# LED.net
KiCad netlist of a schematic drawn in Altium Designer
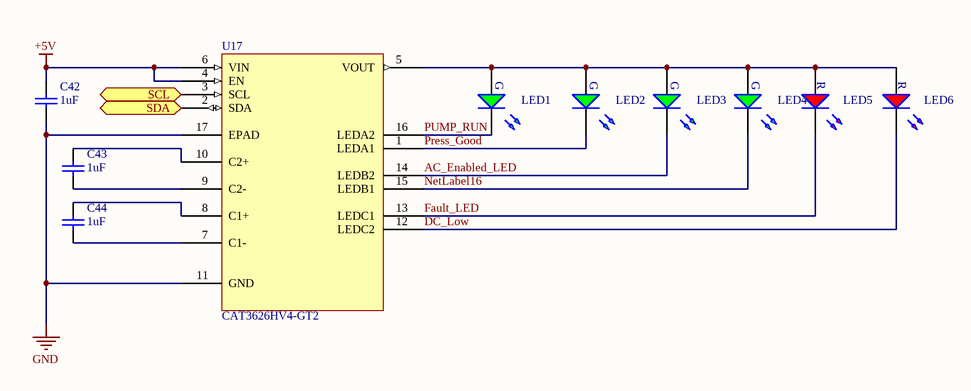
[diagram p0: LED.SchDoc]

(export (version "E")
  (design (tool "Eeschema 10.0.6"))
  (components
    (comp (ref "C42")
      (value "1uF")
      (footprint "0603C")
      (description "CAP CER 1UF 25V X5R 0603")
      (fields
        (field (name "MANUFACTURER") "Samsung Electro-Mechanics")
        (field (name "MANUFACTURER PART NUMBER") "CL10A105KA8NNNC")
      )
      (libsource (lib "RELECTRIFY-PARTSlib_A") (part "Capacitor"))
    )
    (comp (ref "C43")
      (value "1uF")
      (footprint "0603C")
      (description "CAP CER 1UF 25V X5R 0603")
      (fields
        (field (name "MANUFACTURER") "Samsung Electro-Mechanics")
        (field (name "MANUFACTURER PART NUMBER") "CL10A105KA8NNNC")
      )
      (libsource (lib "RELECTRIFY-PARTSlib_A") (part "Capacitor"))
    )
    (comp (ref "C44")
      (value "1uF")
      (footprint "0603C")
      (description "CAP CER 1UF 25V X5R 0603")
      (fields
        (field (name "MANUFACTURER") "Samsung Electro-Mechanics")
        (field (name "MANUFACTURER PART NUMBER") "CL10A105KA8NNNC")
      )
      (libsource (lib "RELECTRIFY-PARTSlib_A") (part "Capacitor"))
    )
    (comp (ref "LED1")
      (value "LED-G")
      (footprint "0805D")
      (description "LED GREEN CLEAR 0805 SMD")
      (fields
        (field (name "MANUFACTURER PART NUMBER") "150080GS75000")
        (field (name "MANUFACTURER") "Würth Elektronik")
      )
      (libsource (lib "RELECTRIFY-PARTSlib_A") (part "LED-G"))
    )
    (comp (ref "LED2")
      (value "LED-G")
      (footprint "0805D")
      (description "LED GREEN CLEAR 0805 SMD")
      (fields
        (field (name "MANUFACTURER PART NUMBER") "150080GS75000")
        (field (name "MANUFACTURER") "Würth Elektronik")
      )
      (libsource (lib "RELECTRIFY-PARTSlib_A") (part "LED-G"))
    )
    (comp (ref "LED3")
      (value "LED-G")
      (footprint "0805D")
      (description "LED GREEN CLEAR 0805 SMD")
      (fields
        (field (name "MANUFACTURER PART NUMBER") "150080GS75000")
        (field (name "MANUFACTURER") "Würth Elektronik")
      )
      (libsource (lib "RELECTRIFY-PARTSlib_A") (part "LED-G"))
    )
    (comp (ref "LED4")
      (value "LED-G")
      (footprint "0805D")
      (description "LED GREEN CLEAR 0805 SMD")
      (fields
        (field (name "MANUFACTURER PART NUMBER") "150080GS75000")
        (field (name "MANUFACTURER") "Würth Elektronik")
      )
      (libsource (lib "RELECTRIFY-PARTSlib_A") (part "LED-G"))
    )
    (comp (ref "LED5")
      (value "LED-R")
      (footprint "0805D")
      (description "LED RED CLEAR 0805 SMD")
      (fields
        (field (name "MANUFACTURER PART NUMBER") "150080RS75000")
        (field (name "MANUFACTURER") "Würth Elektronik")
      )
      (libsource (lib "RELECTRIFY-PARTSlib_A") (part "LED-R"))
    )
    (comp (ref "LED6")
      (value "LED-R")
      (footprint "0805D")
      (description "LED RED CLEAR 0805 SMD")
      (fields
        (field (name "MANUFACTURER PART NUMBER") "150080RS75000")
        (field (name "MANUFACTURER") "Würth Elektronik")
      )
      (libsource (lib "RELECTRIFY-PARTSlib_A") (part "LED-R"))
    )
    (comp (ref "U17")
      (value "CAT3626HV4-GT2")
      (footprint "CAT3626HV4-GT2")
      (fields
        (field (name "MANUFACTURER") "Onsemi")
        (field (name "COPYRIGHT") "Copyright (C) 2022 Ultra Librarian. All rights reserved.")
      )
      (libsource (lib "Database_library") (part "CAT3626HV4-GT2"))
    )
  )
  (nets
    (net (code "1") (name "+5V") (class "Default")
      (node (ref "C42") (pin "2") (pinfunction "2_2") (pintype "passive"))
      (node (ref "U17") (pin "4") (pinfunction "EN_4") (pintype "input"))
      (node (ref "U17") (pin "6") (pinfunction "VIN_6") (pintype "input"))
    )
    (net (code "2") (name "/AC_Enabled_LED") (class "Default")
      (node (ref "LED3") (pin "2") (pinfunction "G_K_2") (pintype "passive"))
      (node (ref "U17") (pin "14") (pinfunction "LEDB2_14") (pintype "passive"))
    )
    (net (code "3") (name "/DC_Low") (class "Default")
      (node (ref "LED6") (pin "2") (pinfunction "R_K_2") (pintype "passive"))
      (node (ref "U17") (pin "12") (pinfunction "LEDC2_12") (pintype "passive"))
    )
    (net (code "4") (name "/Fault_LED") (class "Default")
      (node (ref "LED5") (pin "2") (pinfunction "R_K_2") (pintype "passive"))
      (node (ref "U17") (pin "13") (pinfunction "LEDC1_13") (pintype "passive"))
    )
    (net (code "5") (name "/NetLabel16") (class "Default")
      (node (ref "LED4") (pin "2") (pinfunction "G_K_2") (pintype "passive"))
      (node (ref "U17") (pin "15") (pinfunction "LEDB1_15") (pintype "passive"))
    )
    (net (code "6") (name "/PUMP_RUN") (class "Default")
      (node (ref "LED1") (pin "2") (pinfunction "G_K_2") (pintype "passive"))
      (node (ref "U17") (pin "16") (pinfunction "LEDA2_16") (pintype "passive"))
    )
    (net (code "7") (name "/Press_Good") (class "Default")
      (node (ref "LED2") (pin "2") (pinfunction "G_K_2") (pintype "passive"))
      (node (ref "U17") (pin "1") (pinfunction "LEDA1_1") (pintype "passive"))
    )
    (net (code "8") (name "/SCL") (class "Default")
      (node (ref "U17") (pin "3") (pinfunction "SCL_3") (pintype "input"))
    )
    (net (code "9") (name "/SDA") (class "Default")
      (node (ref "U17") (pin "2") (pinfunction "SDA_2") (pintype "bidirectional"))
    )
    (net (code "10") (name "GND") (class "Default")
      (node (ref "C42") (pin "1") (pinfunction "1_1") (pintype "passive"))
      (node (ref "U17") (pin "11") (pinfunction "GND_11") (pintype "power_in"))
      (node (ref "U17") (pin "17") (pinfunction "EPAD_17") (pintype "passive"))
    )
    (net (code "11") (name "Net-(LED1-G_A)") (class "Default")
      (node (ref "LED1") (pin "1") (pinfunction "G_A_1") (pintype "passive"))
      (node (ref "LED2") (pin "1") (pinfunction "G_A_1") (pintype "passive"))
      (node (ref "LED3") (pin "1") (pinfunction "G_A_1") (pintype "passive"))
      (node (ref "LED4") (pin "1") (pinfunction "G_A_1") (pintype "passive"))
      (node (ref "LED5") (pin "1") (pinfunction "R_A_1") (pintype "passive"))
      (node (ref "LED6") (pin "1") (pinfunction "R_A_1") (pintype "passive"))
      (node (ref "U17") (pin "5") (pinfunction "VOUT_5") (pintype "output"))
    )
    (net (code "12") (name "Net-(U17-C1+)") (class "Default")
      (node (ref "C44") (pin "2") (pinfunction "2_2") (pintype "passive"))
      (node (ref "U17") (pin "8") (pinfunction "C1+_8") (pintype "passive"))
    )
    (net (code "13") (name "Net-(U17-C1-)") (class "Default")
      (node (ref "C44") (pin "1") (pinfunction "1_1") (pintype "passive"))
      (node (ref "U17") (pin "7") (pinfunction "C1-_7") (pintype "passive"))
    )
    (net (code "14") (name "Net-(U17-C2+)") (class "Default")
      (node (ref "C43") (pin "2") (pinfunction "2_2") (pintype "passive"))
      (node (ref "U17") (pin "10") (pinfunction "C2+_10") (pintype "passive"))
    )
    (net (code "15") (name "Net-(U17-C2-)") (class "Default")
      (node (ref "C43") (pin "1") (pinfunction "1_1") (pintype "passive"))
      (node (ref "U17") (pin "9") (pinfunction "C2-_9") (pintype "passive"))
    )
  )
)
